# TOTAL_ON_EAGLE_B.net
KiCad netlist of a schematic drawn in EAGLE
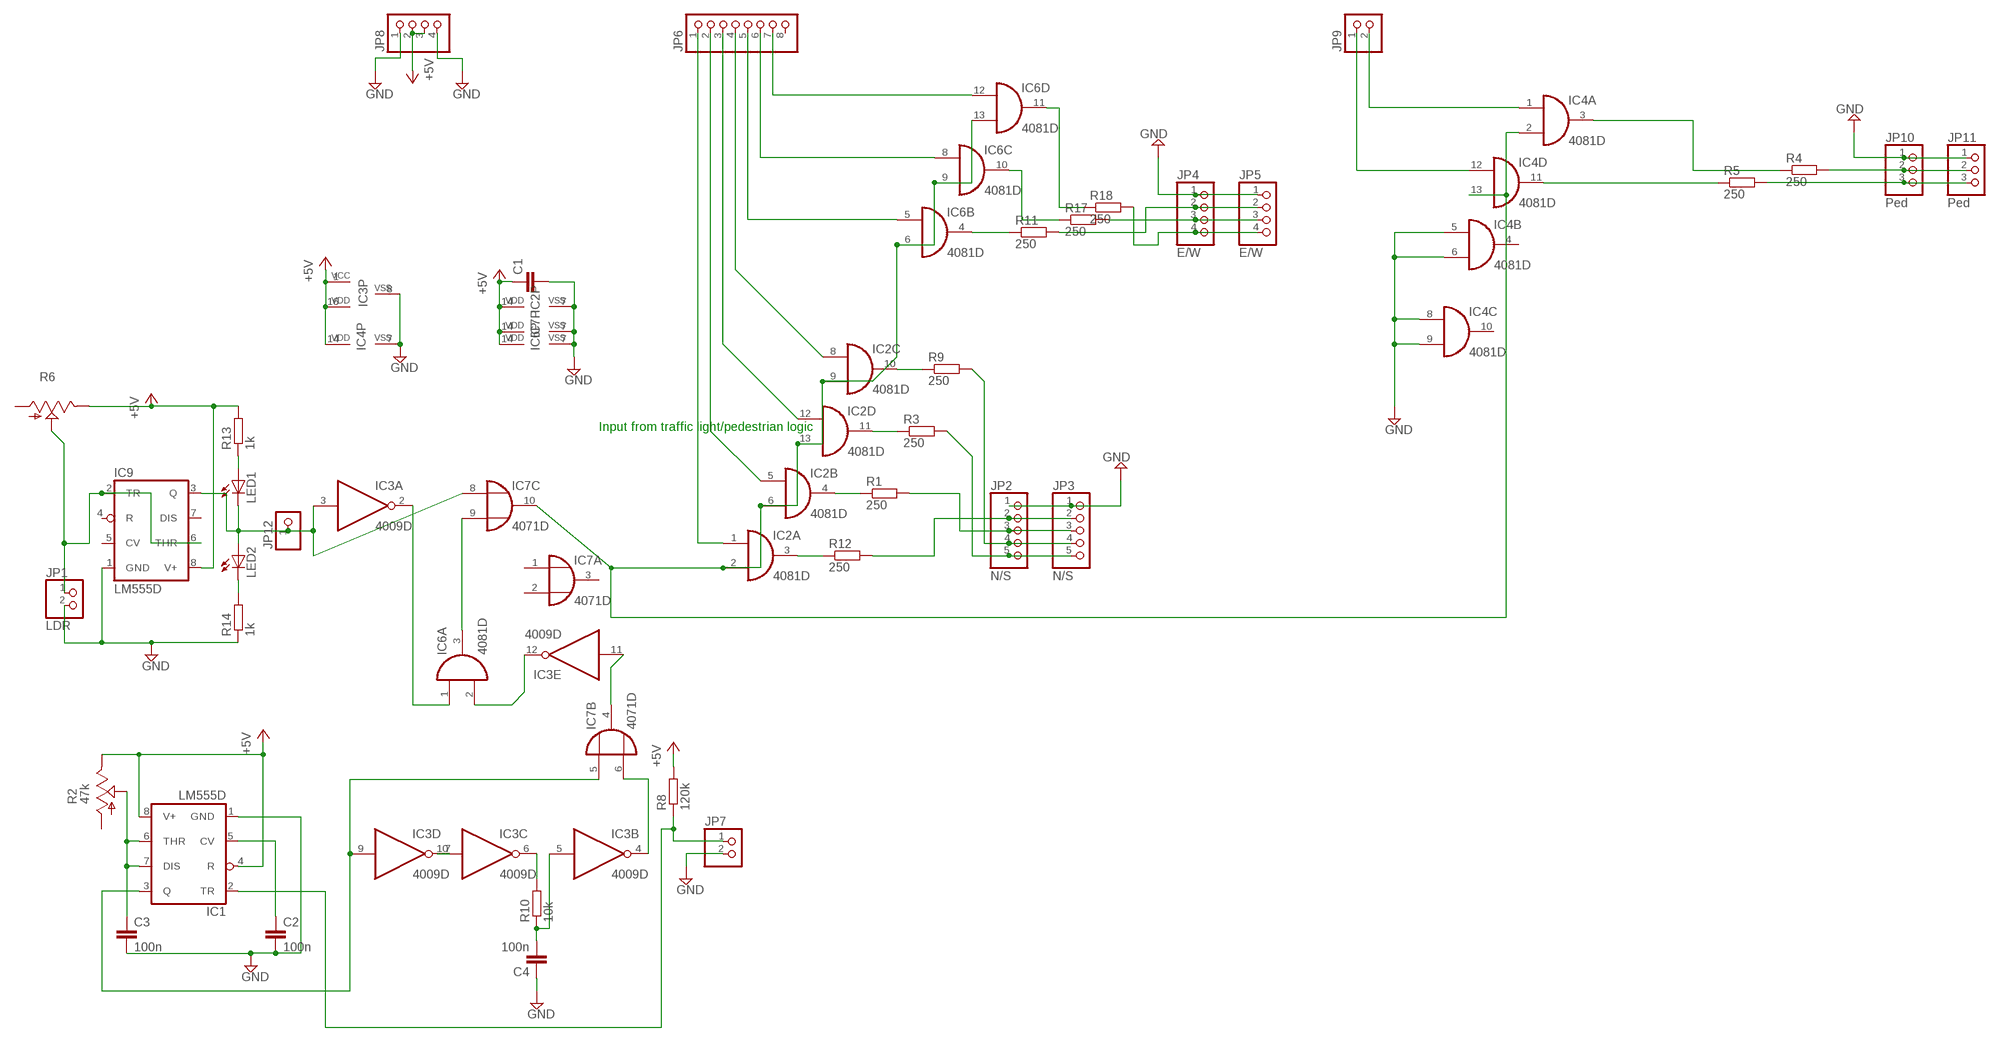
[diagram p0: schematic, sheet 1]

(export (version "E")
  (design (tool "Eeschema 10.0.6"))
  (components
    (comp (ref "C1")
      (value "C-EUC0805")
      (footprint "eagle-import:C0805")
      (libsource (lib "eagle-import") (part "C-EUC0805"))
    )
    (comp (ref "C2")
      (value "100n")
      (footprint "eagle-import:C0805")
      (libsource (lib "eagle-import") (part "C-EUC0805"))
    )
    (comp (ref "C3")
      (value "100n")
      (footprint "eagle-import:C0805")
      (libsource (lib "eagle-import") (part "C-EUC0805"))
    )
    (comp (ref "C4")
      (value "100n")
      (footprint "eagle-import:C0805")
      (libsource (lib "eagle-import") (part "C-EUC0805"))
    )
    (comp (ref "IC1")
      (value "LM555D")
      (footprint "eagle-import:SO08")
      (libsource (lib "eagle-import") (part "555DLM"))
    )
    (comp (ref "IC2")
      (value "4081D")
      (footprint "eagle-import:SO14")
      (libsource (lib "eagle-import") (part "4081D"))
    )
    (comp (ref "IC3")
      (value "4009D")
      (footprint "eagle-import:SO16")
      (libsource (lib "eagle-import") (part "4009D"))
    )
    (comp (ref "IC4")
      (value "4081D")
      (footprint "eagle-import:SO14")
      (libsource (lib "eagle-import") (part "4081D"))
    )
    (comp (ref "IC6")
      (value "4081D")
      (footprint "eagle-import:SO14")
      (libsource (lib "eagle-import") (part "4081D"))
    )
    (comp (ref "IC7")
      (value "4071D")
      (footprint "eagle-import:SO14")
      (libsource (lib "eagle-import") (part "4071D"))
    )
    (comp (ref "IC9")
      (value "LM555D")
      (footprint "eagle-import:SO08")
      (libsource (lib "eagle-import") (part "555DLM"))
    )
    (comp (ref "JP1")
      (value "LDR")
      (footprint "eagle-import:1X02")
      (libsource (lib "eagle-import") (part "PINHD-1X2"))
    )
    (comp (ref "JP2")
      (value "N/S")
      (footprint "eagle-import:1X05")
      (libsource (lib "eagle-import") (part "PINHD-1X5"))
    )
    (comp (ref "JP3")
      (value "N/S")
      (footprint "eagle-import:1X05")
      (libsource (lib "eagle-import") (part "PINHD-1X5"))
    )
    (comp (ref "JP4")
      (value "E/W")
      (footprint "eagle-import:1X04")
      (libsource (lib "eagle-import") (part "PINHD-1X4"))
    )
    (comp (ref "JP5")
      (value "E/W")
      (footprint "eagle-import:1X04")
      (libsource (lib "eagle-import") (part "PINHD-1X4"))
    )
    (comp (ref "JP6")
      (value "PINHD-1X8")
      (footprint "eagle-import:1X08")
      (libsource (lib "eagle-import") (part "PINHD-1X8"))
    )
    (comp (ref "JP7")
      (value "PINHD-1X2")
      (footprint "eagle-import:1X02")
      (libsource (lib "eagle-import") (part "PINHD-1X2"))
    )
    (comp (ref "JP8")
      (value "PINHD-1X4")
      (footprint "eagle-import:1X04")
      (libsource (lib "eagle-import") (part "PINHD-1X4"))
    )
    (comp (ref "JP9")
      (value "PINHD-1X2")
      (footprint "eagle-import:1X02")
      (libsource (lib "eagle-import") (part "PINHD-1X2"))
    )
    (comp (ref "JP10")
      (value "Ped")
      (footprint "eagle-import:1X03")
      (libsource (lib "eagle-import") (part "PINHD-1X3"))
    )
    (comp (ref "JP11")
      (value "Ped")
      (footprint "eagle-import:1X03")
      (libsource (lib "eagle-import") (part "PINHD-1X3"))
    )
    (comp (ref "JP12")
      (value "PINHD-1X1")
      (footprint "eagle-import:1X01")
      (libsource (lib "eagle-import") (part "PINHD-1X1"))
    )
    (comp (ref "LED1")
      (value "LEDSML0805")
      (footprint "eagle-import:SML0805")
      (libsource (lib "eagle-import") (part "LEDSML0805"))
    )
    (comp (ref "LED2")
      (value "LEDSML0805")
      (footprint "eagle-import:SML0805")
      (libsource (lib "eagle-import") (part "LEDSML0805"))
    )
    (comp (ref "R1")
      (value "250")
      (footprint "eagle-import:M0805")
      (libsource (lib "eagle-import") (part "R-EU_M0805"))
    )
    (comp (ref "R2")
      (value "47k")
      (footprint "eagle-import:B64W")
      (libsource (lib "eagle-import") (part "TRIM_US-B64W"))
    )
    (comp (ref "R3")
      (value "250")
      (footprint "eagle-import:M0805")
      (libsource (lib "eagle-import") (part "R-EU_M0805"))
    )
    (comp (ref "R4")
      (value "250")
      (footprint "eagle-import:M0805")
      (libsource (lib "eagle-import") (part "R-EU_M0805"))
    )
    (comp (ref "R5")
      (value "250")
      (footprint "eagle-import:M0805")
      (libsource (lib "eagle-import") (part "R-EU_M0805"))
    )
    (comp (ref "R6")
      (value "TRIM_US-B25P")
      (footprint "eagle-import:B25P")
      (libsource (lib "eagle-import") (part "TRIM_US-B25P"))
    )
    (comp (ref "R8")
      (value "120k")
      (footprint "eagle-import:M0805")
      (libsource (lib "eagle-import") (part "R-EU_M0805"))
    )
    (comp (ref "R9")
      (value "250")
      (footprint "eagle-import:M0805")
      (libsource (lib "eagle-import") (part "R-EU_M0805"))
    )
    (comp (ref "R10")
      (value "10k")
      (footprint "eagle-import:M0805")
      (libsource (lib "eagle-import") (part "R-EU_M0805"))
    )
    (comp (ref "R11")
      (value "250")
      (footprint "eagle-import:M0805")
      (libsource (lib "eagle-import") (part "R-EU_M0805"))
    )
    (comp (ref "R12")
      (value "250")
      (footprint "eagle-import:M0805")
      (libsource (lib "eagle-import") (part "R-EU_M0805"))
    )
    (comp (ref "R13")
      (value "1k")
      (footprint "eagle-import:M0805")
      (libsource (lib "eagle-import") (part "R-EU_M0805"))
    )
    (comp (ref "R14")
      (value "1k")
      (footprint "eagle-import:M0805")
      (libsource (lib "eagle-import") (part "R-EU_M0805"))
    )
    (comp (ref "R17")
      (value "250")
      (footprint "eagle-import:M0805")
      (libsource (lib "eagle-import") (part "R-EU_M0805"))
    )
    (comp (ref "R18")
      (value "250")
      (footprint "eagle-import:M0805")
      (libsource (lib "eagle-import") (part "R-EU_M0805"))
    )
  )
  (nets
    (net (code "1") (name "+5V") (class "Default")
      (node (ref "C1") (pin "1") (pinfunction "1_1") (pintype "passive"))
      (node (ref "IC1") (pin "4") (pinfunction "R_4") (pintype "input"))
      (node (ref "IC1") (pin "8") (pinfunction "V+_8") (pintype "power_in"))
      (node (ref "IC2") (pin "14") (pinfunction "VDD_14") (pintype "power_in"))
      (node (ref "IC3") (pin "1") (pinfunction "VCC_1") (pintype "power_in"))
      (node (ref "IC3") (pin "16") (pinfunction "VDD_16") (pintype "power_in"))
      (node (ref "IC4") (pin "14") (pinfunction "VDD_14") (pintype "power_in"))
      (node (ref "IC6") (pin "14") (pinfunction "VDD_14") (pintype "power_in"))
      (node (ref "IC7") (pin "14") (pinfunction "VDD_14") (pintype "power_in"))
      (node (ref "IC9") (pin "8") (pinfunction "V+_8") (pintype "power_in"))
      (node (ref "JP8") (pin "2") (pinfunction "2_2") (pintype "passive"))
      (node (ref "JP8") (pin "3") (pinfunction "3_3") (pintype "passive"))
      (node (ref "R13") (pin "2") (pinfunction "2_2") (pintype "passive"))
      (node (ref "R2") (pin "E") (pinfunction "E_E") (pintype "passive"))
      (node (ref "R6") (pin "E") (pinfunction "E_E") (pintype "passive"))
      (node (ref "R8") (pin "2") (pinfunction "2_2") (pintype "passive"))
    )
    (net (code "2") (name "GND") (class "Default")
      (node (ref "C1") (pin "2") (pinfunction "2_2") (pintype "passive"))
      (node (ref "C2") (pin "2") (pinfunction "2_2") (pintype "passive"))
      (node (ref "C3") (pin "2") (pinfunction "2_2") (pintype "passive"))
      (node (ref "C4") (pin "1") (pinfunction "1_1") (pintype "passive"))
      (node (ref "IC1") (pin "1") (pinfunction "GND_1") (pintype "power_in"))
      (node (ref "IC2") (pin "7") (pinfunction "VSS_7") (pintype "power_in"))
      (node (ref "IC3") (pin "8") (pinfunction "VSS_8") (pintype "power_in"))
      (node (ref "IC4") (pin "5") (pinfunction "I0_5") (pintype "input"))
      (node (ref "IC4") (pin "6") (pinfunction "I1_6") (pintype "input"))
      (node (ref "IC4") (pin "7") (pinfunction "VSS_7") (pintype "power_in"))
      (node (ref "IC4") (pin "8") (pinfunction "I0_8") (pintype "input"))
      (node (ref "IC4") (pin "9") (pinfunction "I1_9") (pintype "input"))
      (node (ref "IC6") (pin "7") (pinfunction "VSS_7") (pintype "power_in"))
      (node (ref "IC7") (pin "7") (pinfunction "VSS_7") (pintype "power_in"))
      (node (ref "IC9") (pin "1") (pinfunction "GND_1") (pintype "power_in"))
      (node (ref "JP1") (pin "2") (pinfunction "2_2") (pintype "passive"))
      (node (ref "JP10") (pin "1") (pinfunction "1_1") (pintype "passive"))
      (node (ref "JP11") (pin "1") (pinfunction "1_1") (pintype "passive"))
      (node (ref "JP2") (pin "1") (pinfunction "1_1") (pintype "passive"))
      (node (ref "JP3") (pin "1") (pinfunction "1_1") (pintype "passive"))
      (node (ref "JP4") (pin "1") (pinfunction "1_1") (pintype "passive"))
      (node (ref "JP5") (pin "1") (pinfunction "1_1") (pintype "passive"))
      (node (ref "JP7") (pin "2") (pinfunction "2_2") (pintype "passive"))
      (node (ref "JP8") (pin "1") (pinfunction "1_1") (pintype "passive"))
      (node (ref "JP8") (pin "4") (pinfunction "4_4") (pintype "passive"))
      (node (ref "R14") (pin "1") (pinfunction "1_1") (pintype "passive"))
    )
    (net (code "3") (name "Net-(IC1-CV)") (class "Default")
      (node (ref "C2") (pin "1") (pinfunction "1_1") (pintype "passive"))
      (node (ref "IC1") (pin "5") (pinfunction "CV_5") (pintype "input"))
    )
    (net (code "4") (name "Net-(IC1-DIS)") (class "Default")
      (node (ref "C3") (pin "1") (pinfunction "1_1") (pintype "passive"))
      (node (ref "IC1") (pin "6") (pinfunction "THR_6") (pintype "input"))
      (node (ref "IC1") (pin "7") (pinfunction "DIS_7") (pintype "input"))
      (node (ref "R2") (pin "S") (pinfunction "S_S") (pintype "passive"))
    )
    (net (code "5") (name "Net-(IC1-Q)") (class "Default")
      (node (ref "IC1") (pin "3") (pinfunction "Q_3") (pintype "output"))
      (node (ref "IC3") (pin "9") (pinfunction "I_9") (pintype "input"))
      (node (ref "IC7") (pin "5") (pinfunction "I0_5") (pintype "input"))
    )
    (net (code "6") (name "Net-(IC1-TR)") (class "Default")
      (node (ref "IC1") (pin "2") (pinfunction "TR_2") (pintype "input"))
      (node (ref "JP7") (pin "1") (pinfunction "1_1") (pintype "passive"))
      (node (ref "R8") (pin "1") (pinfunction "1_1") (pintype "passive"))
    )
    (net (code "7") (name "Net-(IC2A-I0)") (class "Default")
      (node (ref "IC2") (pin "1") (pinfunction "I0_1") (pintype "input"))
      (node (ref "JP6") (pin "1") (pinfunction "1_1") (pintype "passive"))
    )
    (net (code "8") (name "Net-(IC2A-I1)") (class "Default")
      (node (ref "IC2") (pin "13") (pinfunction "I1_13") (pintype "input"))
      (node (ref "IC2") (pin "2") (pinfunction "I1_2") (pintype "input"))
      (node (ref "IC2") (pin "6") (pinfunction "I1_6") (pintype "input"))
      (node (ref "IC2") (pin "9") (pinfunction "I1_9") (pintype "input"))
      (node (ref "IC4") (pin "13") (pinfunction "I1_13") (pintype "input"))
      (node (ref "IC4") (pin "2") (pinfunction "I1_2") (pintype "input"))
      (node (ref "IC6") (pin "13") (pinfunction "I1_13") (pintype "input"))
      (node (ref "IC6") (pin "6") (pinfunction "I1_6") (pintype "input"))
      (node (ref "IC6") (pin "9") (pinfunction "I1_9") (pintype "input"))
      (node (ref "IC7") (pin "10") (pinfunction "O_10") (pintype "output"))
    )
    (net (code "9") (name "Net-(IC2A-O)") (class "Default")
      (node (ref "IC2") (pin "3") (pinfunction "O_3") (pintype "output"))
      (node (ref "R12") (pin "1") (pinfunction "1_1") (pintype "passive"))
    )
    (net (code "10") (name "Net-(IC2B-I0)") (class "Default")
      (node (ref "IC2") (pin "5") (pinfunction "I0_5") (pintype "input"))
      (node (ref "JP6") (pin "2") (pinfunction "2_2") (pintype "passive"))
    )
    (net (code "11") (name "Net-(IC2B-O)") (class "Default")
      (node (ref "IC2") (pin "4") (pinfunction "O_4") (pintype "output"))
      (node (ref "R1") (pin "1") (pinfunction "1_1") (pintype "passive"))
    )
    (net (code "12") (name "Net-(IC2C-I0)") (class "Default")
      (node (ref "IC2") (pin "8") (pinfunction "I0_8") (pintype "input"))
      (node (ref "JP6") (pin "4") (pinfunction "4_4") (pintype "passive"))
    )
    (net (code "13") (name "Net-(IC2C-O)") (class "Default")
      (node (ref "IC2") (pin "10") (pinfunction "O_10") (pintype "output"))
      (node (ref "R9") (pin "1") (pinfunction "1_1") (pintype "passive"))
    )
    (net (code "14") (name "Net-(IC2D-I0)") (class "Default")
      (node (ref "IC2") (pin "12") (pinfunction "I0_12") (pintype "input"))
      (node (ref "JP6") (pin "3") (pinfunction "3_3") (pintype "passive"))
    )
    (net (code "15") (name "Net-(IC2D-O)") (class "Default")
      (node (ref "IC2") (pin "11") (pinfunction "O_11") (pintype "output"))
      (node (ref "R3") (pin "1") (pinfunction "1_1") (pintype "passive"))
    )
    (net (code "16") (name "Net-(IC3A-I)") (class "Default")
      (node (ref "IC3") (pin "3") (pinfunction "I_3") (pintype "input"))
      (node (ref "IC7") (pin "8") (pinfunction "I0_8") (pintype "input"))
      (node (ref "IC9") (pin "3") (pinfunction "Q_3") (pintype "output"))
      (node (ref "JP12") (pin "1") (pinfunction "1_1") (pintype "passive"))
      (node (ref "LED1") (pin "C") (pinfunction "C_C") (pintype "passive"))
      (node (ref "LED2") (pin "A") (pinfunction "A_A") (pintype "passive"))
    )
    (net (code "17") (name "Net-(IC3A-O)") (class "Default")
      (node (ref "IC3") (pin "2") (pinfunction "O_2") (pintype "output"))
      (node (ref "IC6") (pin "1") (pinfunction "I0_1") (pintype "input"))
    )
    (net (code "18") (name "Net-(IC3B-I)") (class "Default")
      (node (ref "C4") (pin "2") (pinfunction "2_2") (pintype "passive"))
      (node (ref "IC3") (pin "5") (pinfunction "I_5") (pintype "input"))
      (node (ref "R10") (pin "1") (pinfunction "1_1") (pintype "passive"))
    )
    (net (code "19") (name "Net-(IC3B-O)") (class "Default")
      (node (ref "IC3") (pin "4") (pinfunction "O_4") (pintype "output"))
      (node (ref "IC7") (pin "6") (pinfunction "I1_6") (pintype "input"))
    )
    (net (code "20") (name "Net-(IC3C-I)") (class "Default")
      (node (ref "IC3") (pin "10") (pinfunction "O_10") (pintype "output"))
      (node (ref "IC3") (pin "7") (pinfunction "I_7") (pintype "input"))
    )
    (net (code "21") (name "Net-(IC3C-O)") (class "Default")
      (node (ref "IC3") (pin "6") (pinfunction "O_6") (pintype "output"))
      (node (ref "R10") (pin "2") (pinfunction "2_2") (pintype "passive"))
    )
    (net (code "22") (name "Net-(IC3E-I)") (class "Default")
      (node (ref "IC3") (pin "11") (pinfunction "I_11") (pintype "input"))
      (node (ref "IC7") (pin "4") (pinfunction "O_4") (pintype "output"))
    )
    (net (code "23") (name "Net-(IC3E-O)") (class "Default")
      (node (ref "IC3") (pin "12") (pinfunction "O_12") (pintype "output"))
      (node (ref "IC6") (pin "2") (pinfunction "I1_2") (pintype "input"))
    )
    (net (code "24") (name "Net-(IC4A-I0)") (class "Default")
      (node (ref "IC4") (pin "1") (pinfunction "I0_1") (pintype "input"))
      (node (ref "JP9") (pin "2") (pinfunction "2_2") (pintype "passive"))
    )
    (net (code "25") (name "Net-(IC4A-O)") (class "Default")
      (node (ref "IC4") (pin "3") (pinfunction "O_3") (pintype "output"))
      (node (ref "R4") (pin "1") (pinfunction "1_1") (pintype "passive"))
    )
    (net (code "26") (name "Net-(IC4D-I0)") (class "Default")
      (node (ref "IC4") (pin "12") (pinfunction "I0_12") (pintype "input"))
      (node (ref "JP9") (pin "1") (pinfunction "1_1") (pintype "passive"))
    )
    (net (code "27") (name "Net-(IC4D-O)") (class "Default")
      (node (ref "IC4") (pin "11") (pinfunction "O_11") (pintype "output"))
      (node (ref "R5") (pin "1") (pinfunction "1_1") (pintype "passive"))
    )
    (net (code "28") (name "Net-(IC6A-O)") (class "Default")
      (node (ref "IC6") (pin "3") (pinfunction "O_3") (pintype "output"))
      (node (ref "IC7") (pin "9") (pinfunction "I1_9") (pintype "input"))
    )
    (net (code "29") (name "Net-(IC6B-I0)") (class "Default")
      (node (ref "IC6") (pin "5") (pinfunction "I0_5") (pintype "input"))
      (node (ref "JP6") (pin "5") (pinfunction "5_5") (pintype "passive"))
    )
    (net (code "30") (name "Net-(IC6B-O)") (class "Default")
      (node (ref "IC6") (pin "4") (pinfunction "O_4") (pintype "output"))
      (node (ref "R11") (pin "1") (pinfunction "1_1") (pintype "passive"))
    )
    (net (code "31") (name "Net-(IC6C-I0)") (class "Default")
      (node (ref "IC6") (pin "8") (pinfunction "I0_8") (pintype "input"))
      (node (ref "JP6") (pin "6") (pinfunction "6_6") (pintype "passive"))
    )
    (net (code "32") (name "Net-(IC6C-O)") (class "Default")
      (node (ref "IC6") (pin "10") (pinfunction "O_10") (pintype "output"))
      (node (ref "R17") (pin "1") (pinfunction "1_1") (pintype "passive"))
    )
    (net (code "33") (name "Net-(IC6D-I0)") (class "Default")
      (node (ref "IC6") (pin "12") (pinfunction "I0_12") (pintype "input"))
      (node (ref "JP6") (pin "7") (pinfunction "7_7") (pintype "passive"))
    )
    (net (code "34") (name "Net-(IC6D-O)") (class "Default")
      (node (ref "IC6") (pin "11") (pinfunction "O_11") (pintype "output"))
      (node (ref "R18") (pin "1") (pinfunction "1_1") (pintype "passive"))
    )
    (net (code "35") (name "Net-(IC9-THR)") (class "Default")
      (node (ref "IC9") (pin "2") (pinfunction "TR_2") (pintype "input"))
      (node (ref "IC9") (pin "6") (pinfunction "THR_6") (pintype "input"))
      (node (ref "JP1") (pin "1") (pinfunction "1_1") (pintype "passive"))
      (node (ref "R6") (pin "S") (pinfunction "S_S") (pintype "passive"))
    )
    (net (code "36") (name "Net-(JP2-Pad2)") (class "Default")
      (node (ref "JP2") (pin "2") (pinfunction "2_2") (pintype "passive"))
      (node (ref "JP3") (pin "2") (pinfunction "2_2") (pintype "passive"))
      (node (ref "R12") (pin "2") (pinfunction "2_2") (pintype "passive"))
    )
    (net (code "37") (name "Net-(JP2-Pad3)") (class "Default")
      (node (ref "JP2") (pin "3") (pinfunction "3_3") (pintype "passive"))
      (node (ref "JP3") (pin "3") (pinfunction "3_3") (pintype "passive"))
      (node (ref "R1") (pin "2") (pinfunction "2_2") (pintype "passive"))
    )
    (net (code "38") (name "Net-(JP2-Pad4)") (class "Default")
      (node (ref "JP2") (pin "4") (pinfunction "4_4") (pintype "passive"))
      (node (ref "JP3") (pin "4") (pinfunction "4_4") (pintype "passive"))
      (node (ref "R9") (pin "2") (pinfunction "2_2") (pintype "passive"))
    )
    (net (code "39") (name "Net-(JP2-Pad5)") (class "Default")
      (node (ref "JP2") (pin "5") (pinfunction "5_5") (pintype "passive"))
      (node (ref "JP3") (pin "5") (pinfunction "5_5") (pintype "passive"))
      (node (ref "R3") (pin "2") (pinfunction "2_2") (pintype "passive"))
    )
    (net (code "40") (name "Net-(JP4-Pad2)") (class "Default")
      (node (ref "JP4") (pin "2") (pinfunction "2_2") (pintype "passive"))
      (node (ref "JP5") (pin "2") (pinfunction "2_2") (pintype "passive"))
      (node (ref "R11") (pin "2") (pinfunction "2_2") (pintype "passive"))
    )
    (net (code "41") (name "Net-(JP4-Pad3)") (class "Default")
      (node (ref "JP4") (pin "3") (pinfunction "3_3") (pintype "passive"))
      (node (ref "JP5") (pin "3") (pinfunction "3_3") (pintype "passive"))
      (node (ref "R17") (pin "2") (pinfunction "2_2") (pintype "passive"))
    )
    (net (code "42") (name "Net-(JP4-Pad4)") (class "Default")
      (node (ref "JP4") (pin "4") (pinfunction "4_4") (pintype "passive"))
      (node (ref "JP5") (pin "4") (pinfunction "4_4") (pintype "passive"))
      (node (ref "R18") (pin "2") (pinfunction "2_2") (pintype "passive"))
    )
    (net (code "43") (name "Net-(JP10-Pad2)") (class "Default")
      (node (ref "JP10") (pin "2") (pinfunction "2_2") (pintype "passive"))
      (node (ref "JP11") (pin "2") (pinfunction "2_2") (pintype "passive"))
      (node (ref "R4") (pin "2") (pinfunction "2_2") (pintype "passive"))
    )
    (net (code "44") (name "Net-(JP10-Pad3)") (class "Default")
      (node (ref "JP10") (pin "3") (pinfunction "3_3") (pintype "passive"))
      (node (ref "JP11") (pin "3") (pinfunction "3_3") (pintype "passive"))
      (node (ref "R5") (pin "2") (pinfunction "2_2") (pintype "passive"))
    )
    (net (code "45") (name "Net-(LED1-PadA)") (class "Default")
      (node (ref "LED1") (pin "A") (pinfunction "A_A") (pintype "passive"))
      (node (ref "R13") (pin "1") (pinfunction "1_1") (pintype "passive"))
    )
    (net (code "46") (name "Net-(LED2-PadC)") (class "Default")
      (node (ref "LED2") (pin "C") (pinfunction "C_C") (pintype "passive"))
      (node (ref "R14") (pin "2") (pinfunction "2_2") (pintype "passive"))
    )
    (net (code "47") (name "unconnected-(IC4B-O-Pad4)") (class "Default")
      (node (ref "IC4") (pin "4") (pinfunction "O_4") (pintype "output"))
    )
    (net (code "48") (name "unconnected-(IC4C-O-Pad10)") (class "Default")
      (node (ref "IC4") (pin "10") (pinfunction "O_10") (pintype "output"))
    )
    (net (code "49") (name "unconnected-(IC7A-I0-Pad1)") (class "Default")
      (node (ref "IC7") (pin "1") (pinfunction "I0_1") (pintype "input"))
    )
    (net (code "50") (name "unconnected-(IC7A-I1-Pad2)") (class "Default")
      (node (ref "IC7") (pin "2") (pinfunction "I1_2") (pintype "input"))
    )
    (net (code "51") (name "unconnected-(IC7A-O-Pad3)") (class "Default")
      (node (ref "IC7") (pin "3") (pinfunction "O_3") (pintype "output"))
    )
    (net (code "52") (name "unconnected-(IC9-CV-Pad5)") (class "Default")
      (node (ref "IC9") (pin "5") (pinfunction "CV_5") (pintype "input"))
    )
    (net (code "53") (name "unconnected-(IC9-DIS-Pad7)") (class "Default")
      (node (ref "IC9") (pin "7") (pinfunction "DIS_7") (pintype "input"))
    )
    (net (code "54") (name "unconnected-(IC9-R-Pad4)") (class "Default")
      (node (ref "IC9") (pin "4") (pinfunction "R_4") (pintype "input"))
    )
    (net (code "55") (name "unconnected-(JP6-Pad8)") (class "Default")
      (node (ref "JP6") (pin "8") (pinfunction "8_8") (pintype "passive"))
    )
    (net (code "56") (name "unconnected-(R2-PadA)") (class "Default")
      (node (ref "R2") (pin "A") (pinfunction "A_A") (pintype "passive"))
    )
    (net (code "57") (name "unconnected-(R6-PadA)") (class "Default")
      (node (ref "R6") (pin "A") (pinfunction "A_A") (pintype "passive"))
    )
  )
)
